# rgbw-driver.net
KiCad netlist of a schematic drawn in EAGLE
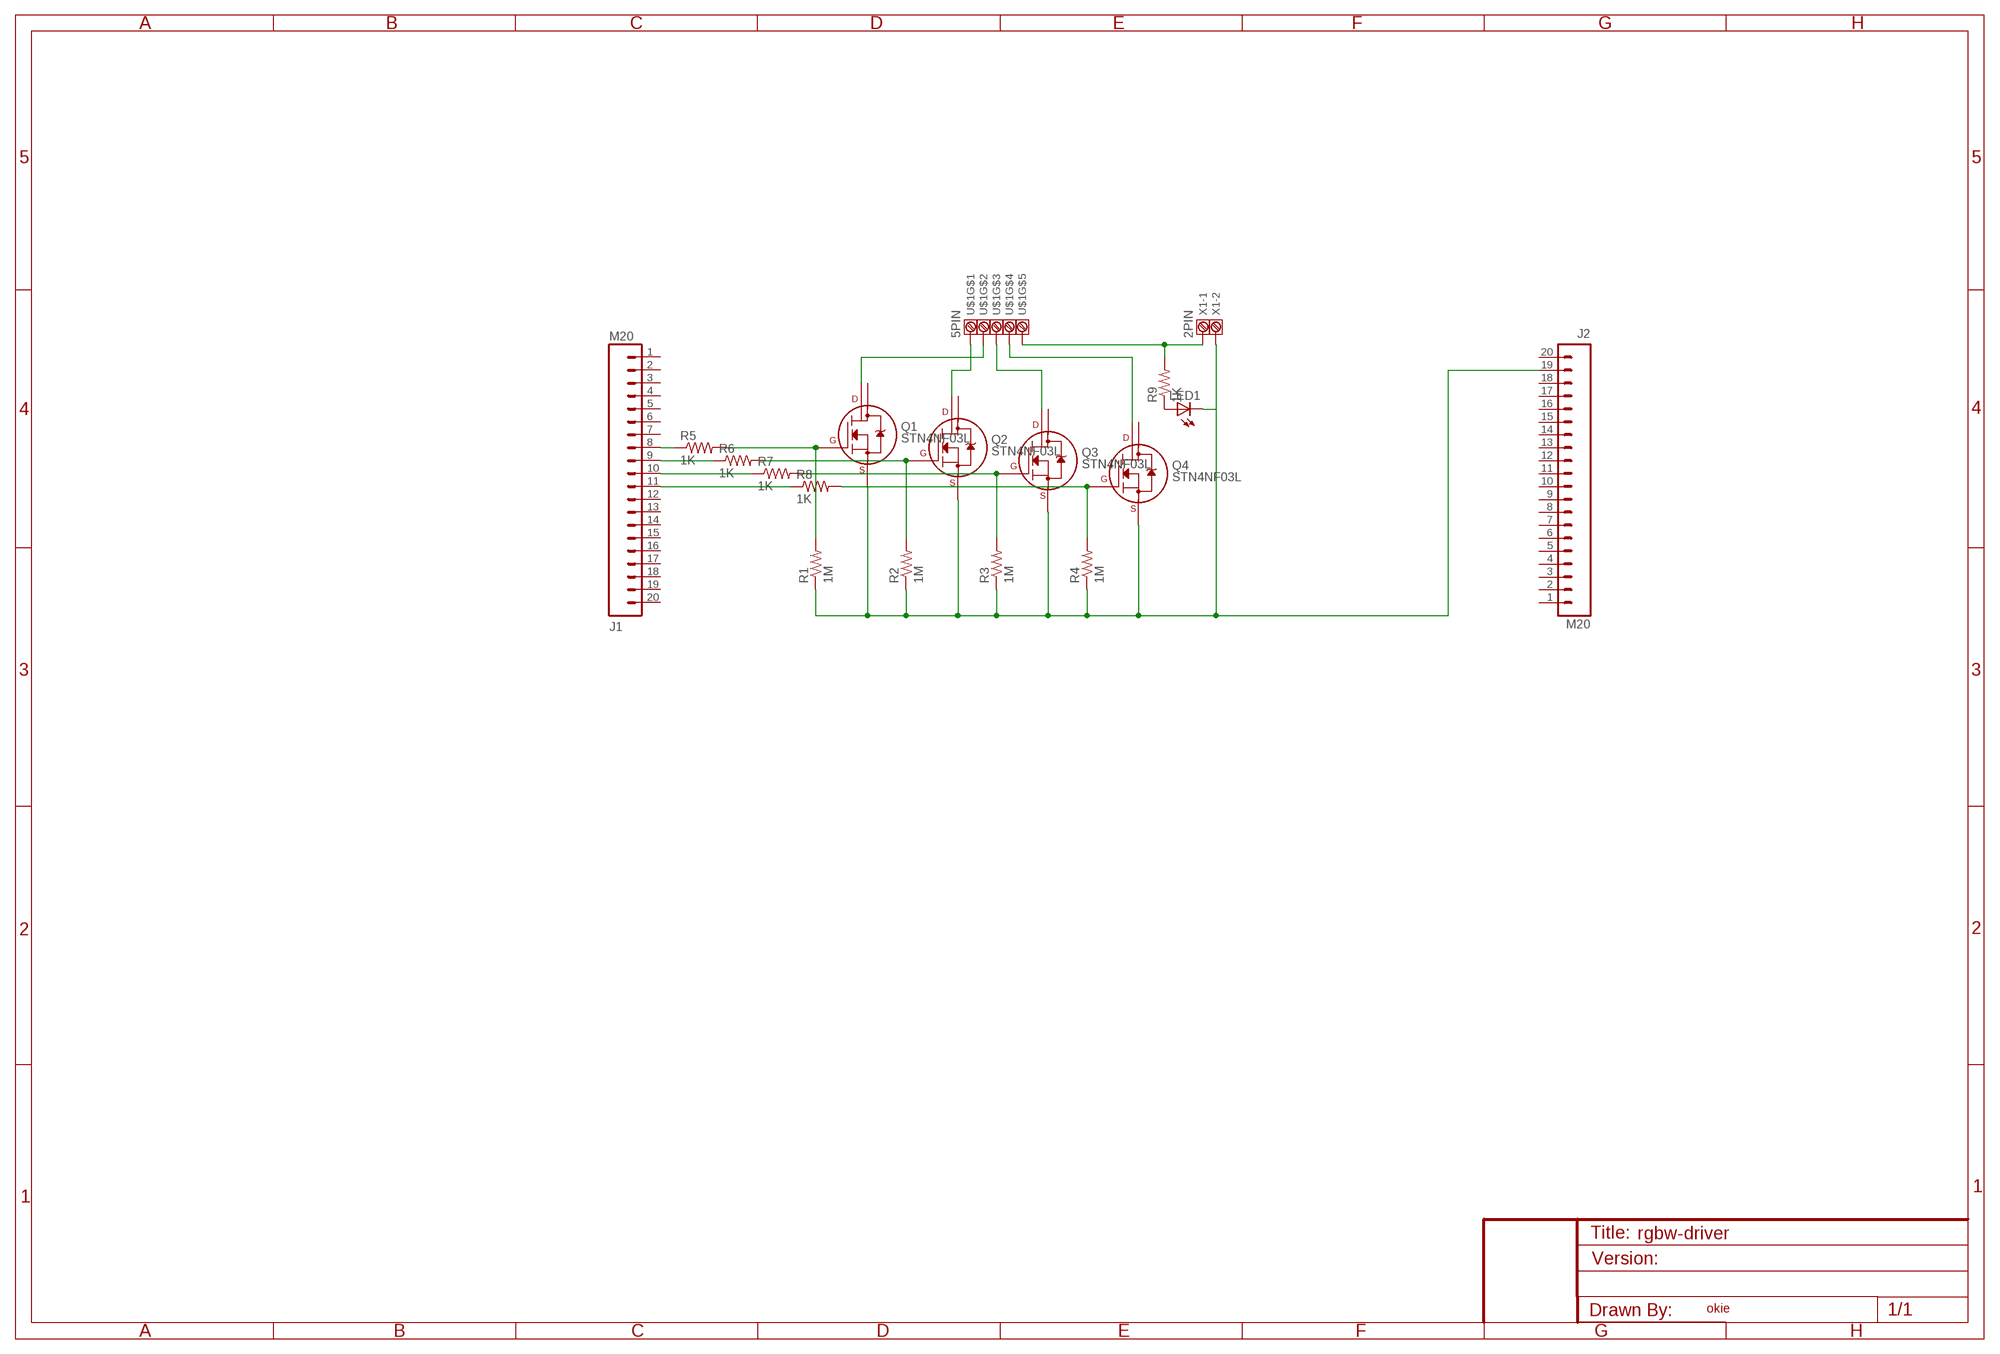
[diagram p0: schematic, sheet 1]

(export (version "E")
  (design (tool "Eeschema 10.0.6"))
  (components
    (comp (ref "J1")
      (value "M20")
      (footprint "eagle-import:1X20")
      (libsource (lib "eagle-import") (part "M20"))
    )
    (comp (ref "J2")
      (value "M20")
      (footprint "eagle-import:1X20")
      (libsource (lib "eagle-import") (part "M20"))
    )
    (comp (ref "LED1")
      (value "LEDCHIP-LED0805")
      (footprint "eagle-import:CHIP-LED0805")
      (libsource (lib "eagle-import") (part "LEDCHIP-LED0805"))
    )
    (comp (ref "Q1")
      (value "STN4NF03L")
      (footprint "eagle-import:SOT-223")
      (libsource (lib "eagle-import") (part "IRLL014"))
    )
    (comp (ref "Q2")
      (value "STN4NF03L")
      (footprint "eagle-import:SOT-223")
      (libsource (lib "eagle-import") (part "IRLL014"))
    )
    (comp (ref "Q3")
      (value "STN4NF03L")
      (footprint "eagle-import:SOT-223")
      (libsource (lib "eagle-import") (part "IRLL014"))
    )
    (comp (ref "Q4")
      (value "STN4NF03L")
      (footprint "eagle-import:SOT-223")
      (libsource (lib "eagle-import") (part "IRLL014"))
    )
    (comp (ref "R1")
      (value "1M")
      (footprint "eagle-import:R0805")
      (libsource (lib "eagle-import") (part "resistor_R-US_R0805"))
    )
    (comp (ref "R2")
      (value "1M")
      (footprint "eagle-import:R0805")
      (libsource (lib "eagle-import") (part "resistor_R-US_R0805"))
    )
    (comp (ref "R3")
      (value "1M")
      (footprint "eagle-import:R0805")
      (libsource (lib "eagle-import") (part "resistor_R-US_R0805"))
    )
    (comp (ref "R4")
      (value "1M")
      (footprint "eagle-import:R0805")
      (libsource (lib "eagle-import") (part "resistor_R-US_R0805"))
    )
    (comp (ref "R5")
      (value "1K")
      (footprint "eagle-import:R0805")
      (libsource (lib "eagle-import") (part "resistor_R-US_R0805"))
    )
    (comp (ref "R6")
      (value "1K")
      (footprint "eagle-import:R0805")
      (libsource (lib "eagle-import") (part "resistor_R-US_R0805"))
    )
    (comp (ref "R7")
      (value "1K")
      (footprint "eagle-import:R0805")
      (libsource (lib "eagle-import") (part "resistor_R-US_R0805"))
    )
    (comp (ref "R8")
      (value "1K")
      (footprint "eagle-import:R0805")
      (libsource (lib "eagle-import") (part "resistor_R-US_R0805"))
    )
    (comp (ref "R9")
      (value "1K")
      (footprint "eagle-import:R0805")
      (libsource (lib "eagle-import") (part "R-US_R0805"))
    )
    (comp (ref "U$1")
      (value "5PIN")
      (footprint "eagle-import:5PIN")
      (libsource (lib "eagle-import") (part "5PIN"))
    )
    (comp (ref "X1")
      (value "2PIN")
      (footprint "eagle-import:2PIN")
      (fields (field (name "MF") "FARNELL") (field (name "MPN") "1727036"))
      (libsource (lib "eagle-import") (part "2PIN"))
    )
  )
  (nets
    (net (code "1") (name "Net-(J1-Pad8)") (class "Default")
      (node (ref "J1") (pin "8") (pinfunction "8_8") (pintype "passive"))
      (node (ref "R5") (pin "1") (pinfunction "1_1") (pintype "passive"))
    )
    (net (code "2") (name "Net-(J1-Pad9)") (class "Default")
      (node (ref "J1") (pin "9") (pinfunction "9_9") (pintype "passive"))
      (node (ref "R6") (pin "1") (pinfunction "1_1") (pintype "passive"))
    )
    (net (code "3") (name "Net-(J1-Pad10)") (class "Default")
      (node (ref "J1") (pin "10") (pinfunction "10_10") (pintype "passive"))
      (node (ref "R7") (pin "1") (pinfunction "1_1") (pintype "passive"))
    )
    (net (code "4") (name "Net-(J1-Pad11)") (class "Default")
      (node (ref "J1") (pin "11") (pinfunction "11_11") (pintype "passive"))
      (node (ref "R8") (pin "1") (pinfunction "1_1") (pintype "passive"))
    )
    (net (code "5") (name "Net-(LED1-PadA)") (class "Default")
      (node (ref "LED1") (pin "A") (pinfunction "A_A") (pintype "passive"))
      (node (ref "R9") (pin "1") (pinfunction "1_1") (pintype "passive"))
    )
    (net (code "6") (name "Net-(Q1-D2)") (class "Default")
      (node (ref "Q1") (pin "4") (pinfunction "D2_4") (pintype "bidirectional"))
      (node (ref "U$1") (pin "2") (pinfunction "1_2") (pintype "passive"))
    )
    (net (code "7") (name "Net-(Q1-G)") (class "Default")
      (node (ref "Q1") (pin "1") (pinfunction "G_1") (pintype "tri_state"))
      (node (ref "R1") (pin "2") (pinfunction "2_2") (pintype "passive"))
      (node (ref "R5") (pin "2") (pinfunction "2_2") (pintype "passive"))
    )
    (net (code "8") (name "Net-(Q1-S)") (class "Default")
      (node (ref "J2") (pin "19") (pinfunction "19_19") (pintype "passive"))
      (node (ref "LED1") (pin "C") (pinfunction "C_C") (pintype "passive"))
      (node (ref "Q1") (pin "3") (pinfunction "S_3") (pintype "bidirectional"))
      (node (ref "Q2") (pin "3") (pinfunction "S_3") (pintype "bidirectional"))
      (node (ref "Q3") (pin "3") (pinfunction "S_3") (pintype "bidirectional"))
      (node (ref "Q4") (pin "3") (pinfunction "S_3") (pintype "bidirectional"))
      (node (ref "R1") (pin "1") (pinfunction "1_1") (pintype "passive"))
      (node (ref "R2") (pin "1") (pinfunction "1_1") (pintype "passive"))
      (node (ref "R3") (pin "1") (pinfunction "1_1") (pintype "passive"))
      (node (ref "R4") (pin "1") (pinfunction "1_1") (pintype "passive"))
      (node (ref "X1") (pin "2") (pinfunction "1_2") (pintype "passive"))
    )
    (net (code "9") (name "Net-(Q2-D2)") (class "Default")
      (node (ref "Q2") (pin "4") (pinfunction "D2_4") (pintype "bidirectional"))
      (node (ref "U$1") (pin "1") (pinfunction "1_1") (pintype "passive"))
    )
    (net (code "10") (name "Net-(Q2-G)") (class "Default")
      (node (ref "Q2") (pin "1") (pinfunction "G_1") (pintype "tri_state"))
      (node (ref "R2") (pin "2") (pinfunction "2_2") (pintype "passive"))
      (node (ref "R6") (pin "2") (pinfunction "2_2") (pintype "passive"))
    )
    (net (code "11") (name "Net-(Q3-D2)") (class "Default")
      (node (ref "Q3") (pin "4") (pinfunction "D2_4") (pintype "bidirectional"))
      (node (ref "U$1") (pin "3") (pinfunction "1_3") (pintype "passive"))
    )
    (net (code "12") (name "Net-(Q3-G)") (class "Default")
      (node (ref "Q3") (pin "1") (pinfunction "G_1") (pintype "tri_state"))
      (node (ref "R3") (pin "2") (pinfunction "2_2") (pintype "passive"))
      (node (ref "R7") (pin "2") (pinfunction "2_2") (pintype "passive"))
    )
    (net (code "13") (name "Net-(Q4-G)") (class "Default")
      (node (ref "Q4") (pin "1") (pinfunction "G_1") (pintype "tri_state"))
      (node (ref "R4") (pin "2") (pinfunction "2_2") (pintype "passive"))
      (node (ref "R8") (pin "2") (pinfunction "2_2") (pintype "passive"))
    )
    (net (code "14") (name "Net-(U$1E-1)") (class "Default")
      (node (ref "R9") (pin "2") (pinfunction "2_2") (pintype "passive"))
      (node (ref "U$1") (pin "5") (pinfunction "1_5") (pintype "passive"))
      (node (ref "X1") (pin "1") (pinfunction "1_1") (pintype "passive"))
    )
    (net (code "15") (name "unconnected-(J1-Pad1)") (class "Default")
      (node (ref "J1") (pin "1") (pinfunction "1_1") (pintype "passive"))
    )
    (net (code "16") (name "unconnected-(J1-Pad2)") (class "Default")
      (node (ref "J1") (pin "2") (pinfunction "2_2") (pintype "passive"))
    )
    (net (code "17") (name "unconnected-(J1-Pad3)") (class "Default")
      (node (ref "J1") (pin "3") (pinfunction "3_3") (pintype "passive"))
    )
    (net (code "18") (name "unconnected-(J1-Pad4)") (class "Default")
      (node (ref "J1") (pin "4") (pinfunction "4_4") (pintype "passive"))
    )
    (net (code "19") (name "unconnected-(J1-Pad5)") (class "Default")
      (node (ref "J1") (pin "5") (pinfunction "5_5") (pintype "passive"))
    )
    (net (code "20") (name "unconnected-(J1-Pad6)") (class "Default")
      (node (ref "J1") (pin "6") (pinfunction "6_6") (pintype "passive"))
    )
    (net (code "21") (name "unconnected-(J1-Pad7)") (class "Default")
      (node (ref "J1") (pin "7") (pinfunction "7_7") (pintype "passive"))
    )
    (net (code "22") (name "unconnected-(J1-Pad12)") (class "Default")
      (node (ref "J1") (pin "12") (pinfunction "12_12") (pintype "passive"))
    )
    (net (code "23") (name "unconnected-(J1-Pad13)") (class "Default")
      (node (ref "J1") (pin "13") (pinfunction "13_13") (pintype "passive"))
    )
    (net (code "24") (name "unconnected-(J1-Pad14)") (class "Default")
      (node (ref "J1") (pin "14") (pinfunction "14_14") (pintype "passive"))
    )
    (net (code "25") (name "unconnected-(J1-Pad15)") (class "Default")
      (node (ref "J1") (pin "15") (pinfunction "15_15") (pintype "passive"))
    )
    (net (code "26") (name "unconnected-(J1-Pad16)") (class "Default")
      (node (ref "J1") (pin "16") (pinfunction "16_16") (pintype "passive"))
    )
    (net (code "27") (name "unconnected-(J1-Pad17)") (class "Default")
      (node (ref "J1") (pin "17") (pinfunction "17_17") (pintype "passive"))
    )
    (net (code "28") (name "unconnected-(J1-Pad18)") (class "Default")
      (node (ref "J1") (pin "18") (pinfunction "18_18") (pintype "passive"))
    )
    (net (code "29") (name "unconnected-(J1-Pad19)") (class "Default")
      (node (ref "J1") (pin "19") (pinfunction "19_19") (pintype "passive"))
    )
    (net (code "30") (name "unconnected-(J1-Pad20)") (class "Default")
      (node (ref "J1") (pin "20") (pinfunction "20_20") (pintype "passive"))
    )
    (net (code "31") (name "unconnected-(J2-Pad1)") (class "Default")
      (node (ref "J2") (pin "1") (pinfunction "1_1") (pintype "passive"))
    )
    (net (code "32") (name "unconnected-(J2-Pad2)") (class "Default")
      (node (ref "J2") (pin "2") (pinfunction "2_2") (pintype "passive"))
    )
    (net (code "33") (name "unconnected-(J2-Pad3)") (class "Default")
      (node (ref "J2") (pin "3") (pinfunction "3_3") (pintype "passive"))
    )
    (net (code "34") (name "unconnected-(J2-Pad4)") (class "Default")
      (node (ref "J2") (pin "4") (pinfunction "4_4") (pintype "passive"))
    )
    (net (code "35") (name "unconnected-(J2-Pad5)") (class "Default")
      (node (ref "J2") (pin "5") (pinfunction "5_5") (pintype "passive"))
    )
    (net (code "36") (name "unconnected-(J2-Pad6)") (class "Default")
      (node (ref "J2") (pin "6") (pinfunction "6_6") (pintype "passive"))
    )
    (net (code "37") (name "unconnected-(J2-Pad7)") (class "Default")
      (node (ref "J2") (pin "7") (pinfunction "7_7") (pintype "passive"))
    )
    (net (code "38") (name "unconnected-(J2-Pad8)") (class "Default")
      (node (ref "J2") (pin "8") (pinfunction "8_8") (pintype "passive"))
    )
    (net (code "39") (name "unconnected-(J2-Pad9)") (class "Default")
      (node (ref "J2") (pin "9") (pinfunction "9_9") (pintype "passive"))
    )
    (net (code "40") (name "unconnected-(J2-Pad10)") (class "Default")
      (node (ref "J2") (pin "10") (pinfunction "10_10") (pintype "passive"))
    )
    (net (code "41") (name "unconnected-(J2-Pad11)") (class "Default")
      (node (ref "J2") (pin "11") (pinfunction "11_11") (pintype "passive"))
    )
    (net (code "42") (name "unconnected-(J2-Pad12)") (class "Default")
      (node (ref "J2") (pin "12") (pinfunction "12_12") (pintype "passive"))
    )
    (net (code "43") (name "unconnected-(J2-Pad13)") (class "Default")
      (node (ref "J2") (pin "13") (pinfunction "13_13") (pintype "passive"))
    )
    (net (code "44") (name "unconnected-(J2-Pad14)") (class "Default")
      (node (ref "J2") (pin "14") (pinfunction "14_14") (pintype "passive"))
    )
    (net (code "45") (name "unconnected-(J2-Pad15)") (class "Default")
      (node (ref "J2") (pin "15") (pinfunction "15_15") (pintype "passive"))
    )
    (net (code "46") (name "unconnected-(J2-Pad16)") (class "Default")
      (node (ref "J2") (pin "16") (pinfunction "16_16") (pintype "passive"))
    )
    (net (code "47") (name "unconnected-(J2-Pad17)") (class "Default")
      (node (ref "J2") (pin "17") (pinfunction "17_17") (pintype "passive"))
    )
    (net (code "48") (name "unconnected-(J2-Pad18)") (class "Default")
      (node (ref "J2") (pin "18") (pinfunction "18_18") (pintype "passive"))
    )
    (net (code "49") (name "unconnected-(J2-Pad20)") (class "Default")
      (node (ref "J2") (pin "20") (pinfunction "20_20") (pintype "passive"))
    )
    (net (code "50") (name "unconnected-(Q1-D1-Pad2)") (class "Default")
      (node (ref "Q1") (pin "2") (pinfunction "D1_2") (pintype "bidirectional"))
    )
    (net (code "51") (name "unconnected-(Q2-D1-Pad2)") (class "Default")
      (node (ref "Q2") (pin "2") (pinfunction "D1_2") (pintype "bidirectional"))
    )
    (net (code "52") (name "unconnected-(Q3-D1-Pad2)") (class "Default")
      (node (ref "Q3") (pin "2") (pinfunction "D1_2") (pintype "bidirectional"))
    )
    (net (code "53") (name "unconnected-(Q4-D1-Pad2)") (class "Default")
      (node (ref "Q4") (pin "2") (pinfunction "D1_2") (pintype "bidirectional"))
    )
    (net (code "54") (name "unconnected-(Q4-D2-Pad4)") (class "Default")
      (node (ref "Q4") (pin "4") (pinfunction "D2_4") (pintype "bidirectional"))
    )
    (net (code "55") (name "unconnected-(U$1D-1-Pad4)") (class "Default")
      (node (ref "U$1") (pin "4") (pinfunction "1_4") (pintype "passive"))
    )
  )
)
